# basspre.net
KiCad netlist of a schematic drawn in EAGLE
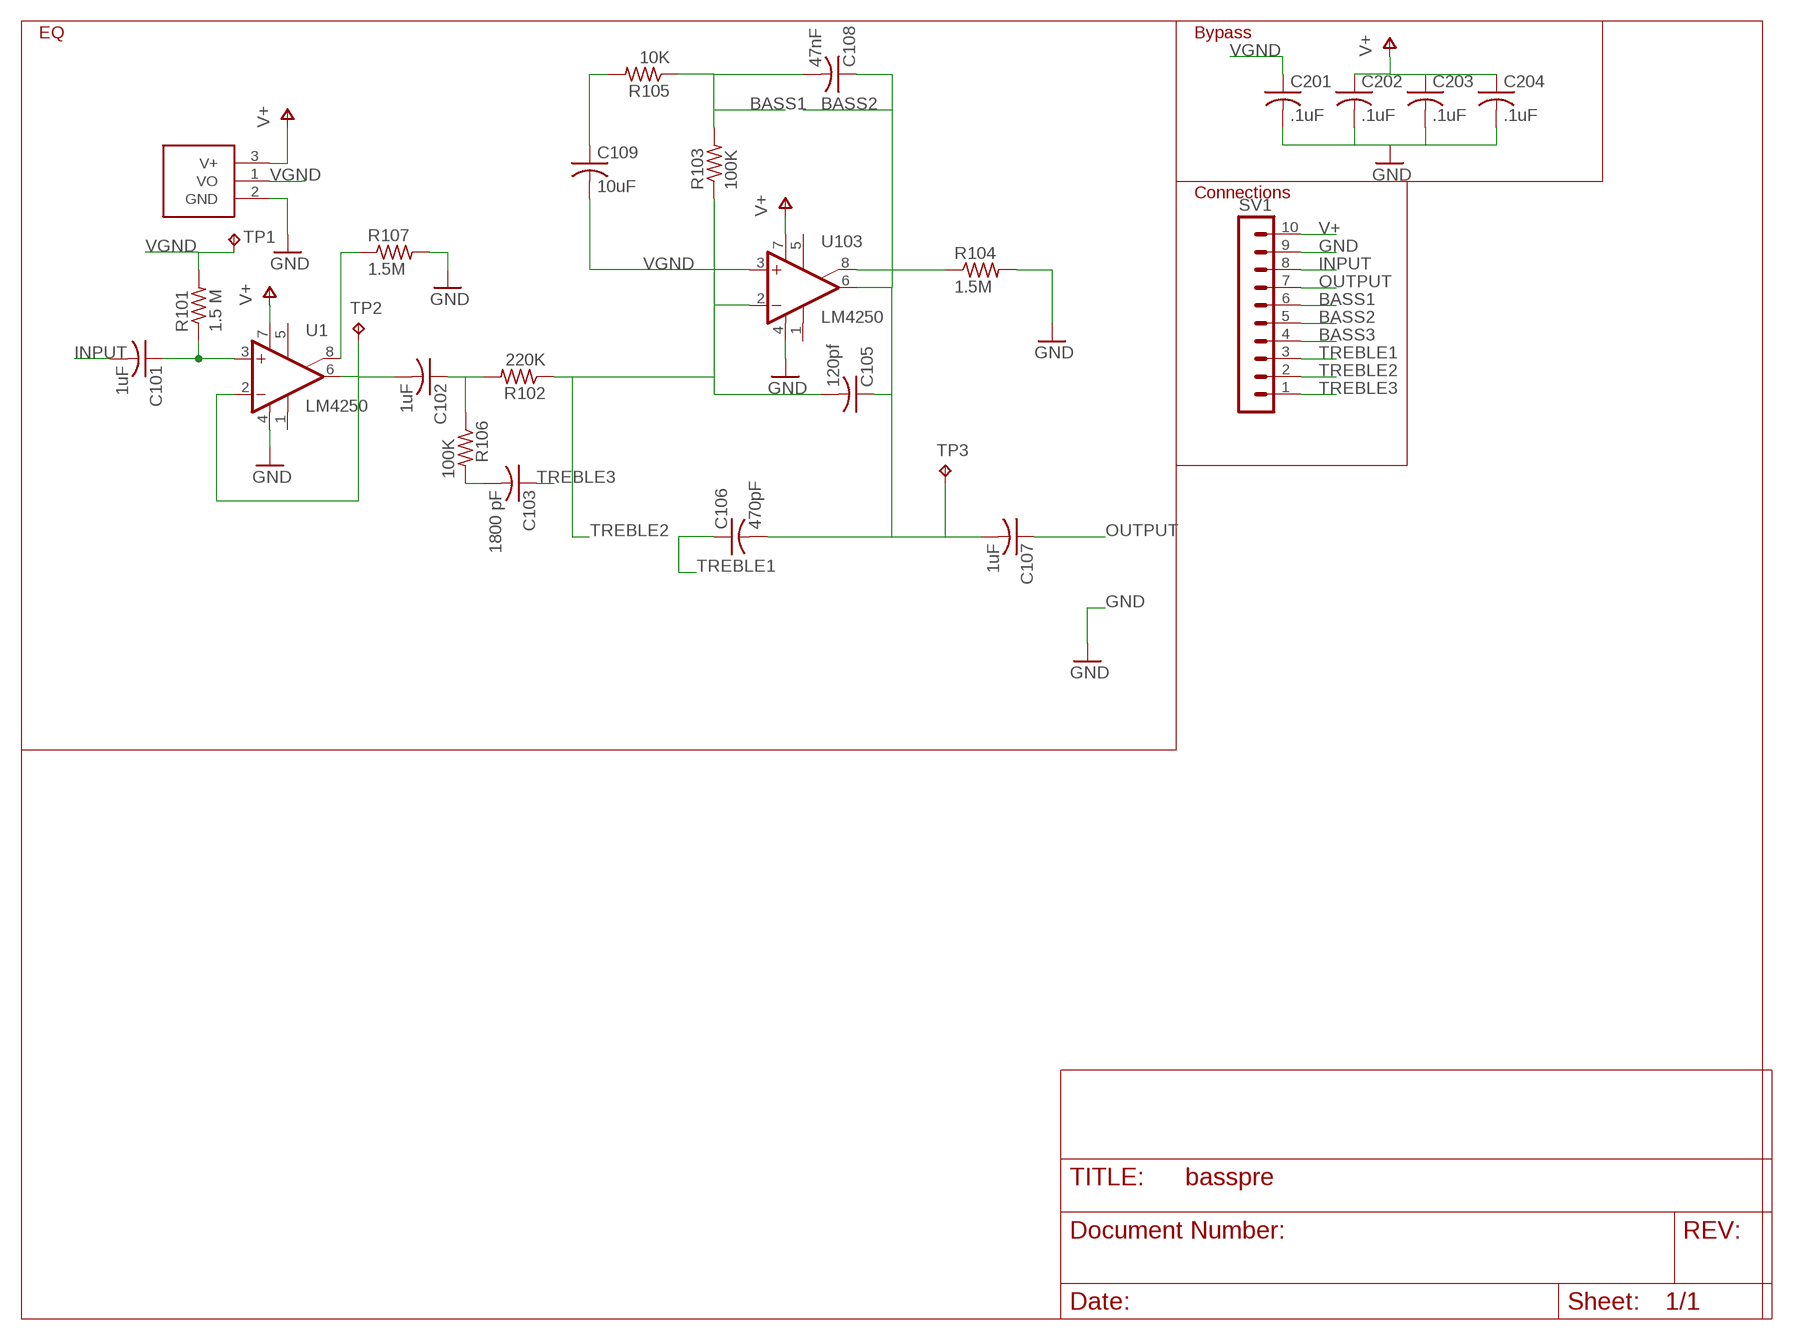
[diagram p0: schematic, sheet 1]

(export (version "E")
  (design (tool "Eeschema 10.0.6"))
  (components
    (comp (ref "C101")
      (value "1uF")
      (footprint "eagle-import:C0805")
      (libsource (lib "eagle-import") (part "C-USC0805"))
    )
    (comp (ref "C102")
      (value "1uF")
      (footprint "eagle-import:C0805")
      (libsource (lib "eagle-import") (part "C-USC0805"))
    )
    (comp (ref "C103")
      (value "1800 pF")
      (footprint "eagle-import:C0603")
      (libsource (lib "eagle-import") (part "resistor_C-USC0603"))
    )
    (comp (ref "C105")
      (value "120pf")
      (footprint "eagle-import:C0603")
      (libsource (lib "eagle-import") (part "resistor_C-USC0603"))
    )
    (comp (ref "C106")
      (value "470pF")
      (footprint "eagle-import:C0603")
      (libsource (lib "eagle-import") (part "resistor_C-USC0603"))
    )
    (comp (ref "C107")
      (value "1uF")
      (footprint "eagle-import:C0805")
      (libsource (lib "eagle-import") (part "C-USC0805"))
    )
    (comp (ref "C108")
      (value "47nF")
      (footprint "eagle-import:C0603")
      (libsource (lib "eagle-import") (part "resistor_C-USC0603"))
    )
    (comp (ref "C109")
      (value "10uF")
      (footprint "eagle-import:C0805")
      (libsource (lib "eagle-import") (part "C-USC0805"))
    )
    (comp (ref "C201")
      (value ".1uF")
      (footprint "eagle-import:C0603")
      (libsource (lib "eagle-import") (part "resistor_C-USC0603"))
    )
    (comp (ref "C202")
      (value ".1uF")
      (footprint "eagle-import:C0603")
      (libsource (lib "eagle-import") (part "resistor_C-USC0603"))
    )
    (comp (ref "C203")
      (value ".1uF")
      (footprint "eagle-import:C0603")
      (libsource (lib "eagle-import") (part "resistor_C-USC0603"))
    )
    (comp (ref "C204")
      (value ".1uF")
      (footprint "eagle-import:C0603")
      (libsource (lib "eagle-import") (part "resistor_C-USC0603"))
    )
    (comp (ref "R101")
      (value "1.5 M")
      (footprint "eagle-import:R0603")
      (libsource (lib "eagle-import") (part "R-US_R0603"))
    )
    (comp (ref "R102")
      (value "220K")
      (footprint "eagle-import:R0603")
      (libsource (lib "eagle-import") (part "R-US_R0603"))
    )
    (comp (ref "R103")
      (value "100K")
      (footprint "eagle-import:R0603")
      (libsource (lib "eagle-import") (part "R-US_R0603"))
    )
    (comp (ref "R104")
      (value "1.5M")
      (footprint "eagle-import:R0603")
      (libsource (lib "eagle-import") (part "R-US_R0603"))
    )
    (comp (ref "R105")
      (value "10K")
      (footprint "eagle-import:R0603")
      (libsource (lib "eagle-import") (part "R-US_R0603"))
    )
    (comp (ref "R106")
      (value "100K")
      (footprint "eagle-import:R0603")
      (libsource (lib "eagle-import") (part "R-US_R0603"))
    )
    (comp (ref "R107")
      (value "1.5M")
      (footprint "eagle-import:R0603")
      (libsource (lib "eagle-import") (part "R-US_R0603"))
    )
    (comp (ref "SV1")
      (value "MA10-1")
      (footprint "eagle-import:MA10-1")
      (libsource (lib "eagle-import") (part "MA10-1"))
    )
    (comp (ref "TP1")
      (value "TPPAD1-13")
      (footprint "eagle-import:P1-13")
      (libsource (lib "eagle-import") (part "TPPAD1-13"))
    )
    (comp (ref "TP2")
      (value "TPPAD1-13")
      (footprint "eagle-import:P1-13")
      (libsource (lib "eagle-import") (part "TPPAD1-13"))
    )
    (comp (ref "TP3")
      (value "TPPAD1-13")
      (footprint "eagle-import:P1-13")
      (libsource (lib "eagle-import") (part "TPPAD1-13"))
    )
    (comp (ref "U1")
      (value "LM4250")
      (footprint "eagle-import:SOIC8")
      (libsource (lib "eagle-import") (part "LM4250"))
    )
    (comp (ref "U101")
      (value "TLE2426IDR")
      (footprint "eagle-import:SOIC8")
      (libsource (lib "eagle-import") (part "TLE2426IDR"))
    )
    (comp (ref "U103")
      (value "LM4250")
      (footprint "eagle-import:SOIC8")
      (libsource (lib "eagle-import") (part "LM4250"))
    )
  )
  (nets
    (net (code "1") (name "/BASS1") (class "Default")
      (node (ref "C108") (pin "2") (pinfunction "2_2") (pintype "passive"))
      (node (ref "R103") (pin "2") (pinfunction "2_2") (pintype "passive"))
      (node (ref "R105") (pin "1") (pinfunction "1_1") (pintype "passive"))
      (node (ref "SV1") (pin "6") (pinfunction "6_6") (pintype "passive"))
    )
    (net (code "2") (name "/BASS2") (class "Default")
      (node (ref "C105") (pin "1") (pinfunction "1_1") (pintype "passive"))
      (node (ref "C106") (pin "2") (pinfunction "2_2") (pintype "passive"))
      (node (ref "C107") (pin "2") (pinfunction "2_2") (pintype "passive"))
      (node (ref "C108") (pin "1") (pinfunction "1_1") (pintype "passive"))
      (node (ref "SV1") (pin "5") (pinfunction "5_5") (pintype "passive"))
      (node (ref "TP3") (pin "TP") (pinfunction "TP_TP") (pintype "input"))
      (node (ref "U103") (pin "6") (pinfunction "OUT_6") (pintype "output"))
    )
    (net (code "3") (name "/BASS3") (class "Default")
      (node (ref "SV1") (pin "4") (pinfunction "4_4") (pintype "passive"))
    )
    (net (code "4") (name "/INPUT") (class "Default")
      (node (ref "C101") (pin "2") (pinfunction "2_2") (pintype "passive"))
      (node (ref "SV1") (pin "8") (pinfunction "8_8") (pintype "passive"))
    )
    (net (code "5") (name "/OUTPUT") (class "Default")
      (node (ref "C107") (pin "1") (pinfunction "1_1") (pintype "passive"))
      (node (ref "SV1") (pin "7") (pinfunction "7_7") (pintype "passive"))
    )
    (net (code "6") (name "/TREBLE1") (class "Default")
      (node (ref "C106") (pin "1") (pinfunction "1_1") (pintype "passive"))
      (node (ref "SV1") (pin "3") (pinfunction "3_3") (pintype "passive"))
    )
    (net (code "7") (name "/TREBLE2") (class "Default")
      (node (ref "C105") (pin "2") (pinfunction "2_2") (pintype "passive"))
      (node (ref "R102") (pin "1") (pinfunction "1_1") (pintype "passive"))
      (node (ref "R103") (pin "1") (pinfunction "1_1") (pintype "passive"))
      (node (ref "SV1") (pin "2") (pinfunction "2_2") (pintype "passive"))
      (node (ref "U103") (pin "2") (pinfunction "-IN_2") (pintype "input"))
    )
    (net (code "8") (name "/TREBLE3") (class "Default")
      (node (ref "C103") (pin "1") (pinfunction "1_1") (pintype "passive"))
      (node (ref "SV1") (pin "1") (pinfunction "1_1") (pintype "passive"))
    )
    (net (code "9") (name "/VGND") (class "Default")
      (node (ref "C109") (pin "2") (pinfunction "2_2") (pintype "passive"))
      (node (ref "C201") (pin "1") (pinfunction "1_1") (pintype "passive"))
      (node (ref "R101") (pin "2") (pinfunction "2_2") (pintype "passive"))
      (node (ref "TP1") (pin "TP") (pinfunction "TP_TP") (pintype "input"))
      (node (ref "U101") (pin "1") (pinfunction "VO_1") (pintype "bidirectional"))
      (node (ref "U103") (pin "3") (pinfunction "+IN_3") (pintype "input"))
    )
    (net (code "10") (name "GND") (class "Default")
      (node (ref "C201") (pin "2") (pinfunction "2_2") (pintype "passive"))
      (node (ref "C202") (pin "2") (pinfunction "2_2") (pintype "passive"))
      (node (ref "C203") (pin "2") (pinfunction "2_2") (pintype "passive"))
      (node (ref "C204") (pin "2") (pinfunction "2_2") (pintype "passive"))
      (node (ref "R104") (pin "2") (pinfunction "2_2") (pintype "passive"))
      (node (ref "R107") (pin "2") (pinfunction "2_2") (pintype "passive"))
      (node (ref "SV1") (pin "9") (pinfunction "9_9") (pintype "passive"))
      (node (ref "U1") (pin "4") (pinfunction "V-_4") (pintype "power_in"))
      (node (ref "U101") (pin "2") (pinfunction "GND_2") (pintype "bidirectional"))
      (node (ref "U103") (pin "4") (pinfunction "V-_4") (pintype "power_in"))
    )
    (net (code "11") (name "Net-(C102-Pad1)") (class "Default")
      (node (ref "C102") (pin "1") (pinfunction "1_1") (pintype "passive"))
      (node (ref "R102") (pin "2") (pinfunction "2_2") (pintype "passive"))
      (node (ref "R106") (pin "1") (pinfunction "1_1") (pintype "passive"))
    )
    (net (code "12") (name "Net-(C103-Pad2)") (class "Default")
      (node (ref "C103") (pin "2") (pinfunction "2_2") (pintype "passive"))
      (node (ref "R106") (pin "2") (pinfunction "2_2") (pintype "passive"))
    )
    (net (code "13") (name "Net-(C109-Pad1)") (class "Default")
      (node (ref "C109") (pin "1") (pinfunction "1_1") (pintype "passive"))
      (node (ref "R105") (pin "2") (pinfunction "2_2") (pintype "passive"))
    )
    (net (code "14") (name "Net-(U1-+IN)") (class "Default")
      (node (ref "C101") (pin "1") (pinfunction "1_1") (pintype "passive"))
      (node (ref "R101") (pin "1") (pinfunction "1_1") (pintype "passive"))
      (node (ref "U1") (pin "3") (pinfunction "+IN_3") (pintype "input"))
    )
    (net (code "15") (name "Net-(U1--IN)") (class "Default")
      (node (ref "C102") (pin "2") (pinfunction "2_2") (pintype "passive"))
      (node (ref "TP2") (pin "TP") (pinfunction "TP_TP") (pintype "input"))
      (node (ref "U1") (pin "2") (pinfunction "-IN_2") (pintype "input"))
      (node (ref "U1") (pin "6") (pinfunction "OUT_6") (pintype "output"))
    )
    (net (code "16") (name "Net-(U1-CURRENT)") (class "Default")
      (node (ref "R107") (pin "1") (pinfunction "1_1") (pintype "passive"))
      (node (ref "U1") (pin "8") (pinfunction "CURRENT_8") (pintype "passive"))
    )
    (net (code "17") (name "Net-(U103-CURRENT)") (class "Default")
      (node (ref "R104") (pin "1") (pinfunction "1_1") (pintype "passive"))
      (node (ref "U103") (pin "8") (pinfunction "CURRENT_8") (pintype "passive"))
    )
    (net (code "18") (name "V+") (class "Default")
      (node (ref "C202") (pin "1") (pinfunction "1_1") (pintype "passive"))
      (node (ref "C203") (pin "1") (pinfunction "1_1") (pintype "passive"))
      (node (ref "C204") (pin "1") (pinfunction "1_1") (pintype "passive"))
      (node (ref "SV1") (pin "10") (pinfunction "10_10") (pintype "passive"))
      (node (ref "U1") (pin "7") (pinfunction "V+_7") (pintype "power_in"))
      (node (ref "U101") (pin "3") (pinfunction "V+_3") (pintype "bidirectional"))
      (node (ref "U103") (pin "7") (pinfunction "V+_7") (pintype "power_in"))
    )
    (net (code "19") (name "unconnected-(U1-OFF--Pad1)") (class "Default")
      (node (ref "U1") (pin "1") (pinfunction "OFF-_1") (pintype "passive"))
    )
    (net (code "20") (name "unconnected-(U1-OFF-Pad5)") (class "Default")
      (node (ref "U1") (pin "5") (pinfunction "OFF_5") (pintype "passive"))
    )
    (net (code "21") (name "unconnected-(U103-OFF--Pad1)") (class "Default")
      (node (ref "U103") (pin "1") (pinfunction "OFF-_1") (pintype "passive"))
    )
    (net (code "22") (name "unconnected-(U103-OFF-Pad5)") (class "Default")
      (node (ref "U103") (pin "5") (pinfunction "OFF_5") (pintype "passive"))
    )
  )
)
